# eCore_MCU.net
KiCad netlist of a schematic drawn in Altium Designer
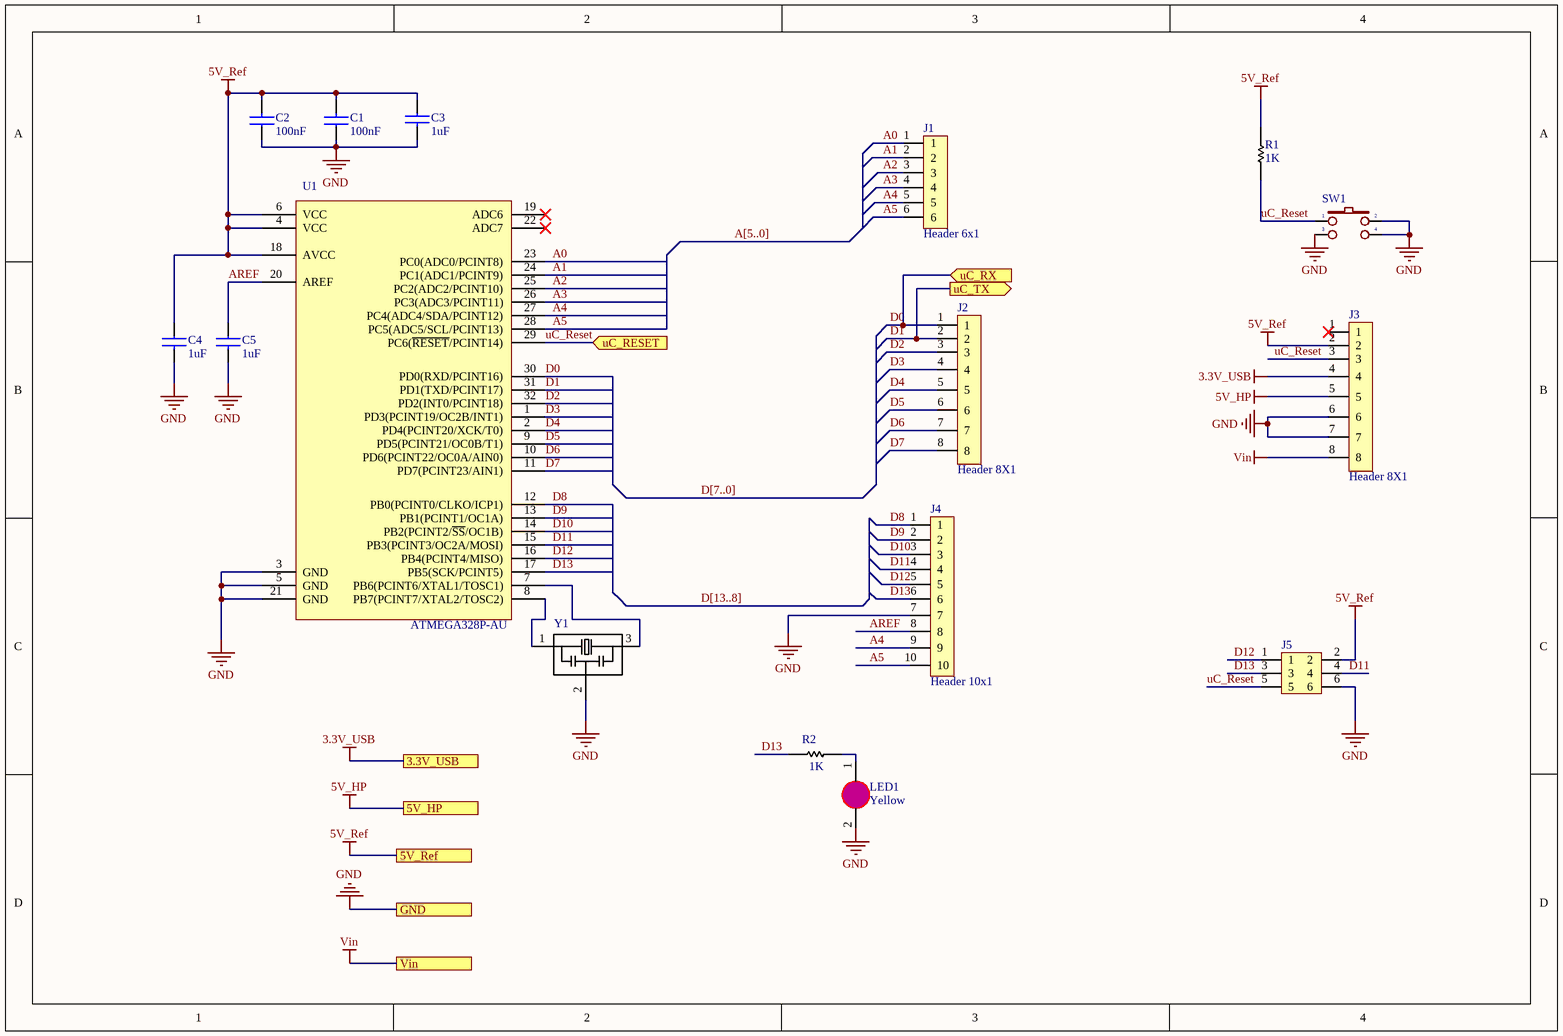
[diagram p0: eCore_MCU.SchDoc]

(export (version "E")
  (design (tool "Eeschema 10.0.6"))
  (components
    (comp (ref "C1")
      (value "100nF")
      (footprint "CAPC1005X60N")
      (libsource (lib "SCHP-CAD") (part "Cap 0402"))
    )
    (comp (ref "C2")
      (value "100nF")
      (footprint "CAPC1005X60N")
      (libsource (lib "SCHP-CAD") (part "Cap 0402"))
    )
    (comp (ref "C3") (value "1uF") (footprint "C0603") (libsource (lib "SCHP-CAD") (part "Cap 0603")))
    (comp (ref "C4") (value "1uF") (footprint "CAPC1005X60N") (libsource (lib "SCHP-CAD") (part "Cap 0402")))
    (comp (ref "C5") (value "1uF") (footprint "CAPC1005X60N") (libsource (lib "SCHP-CAD") (part "Cap 0402")))
    (comp (ref "J1")
      (value "Header 6x1")
      (footprint "1x6 Socket Heder 2.54mm")
      (libsource (lib "SCHP-CAD") (part "Header 6x1"))
    )
    (comp (ref "J2")
      (value "Header 8X1")
      (footprint "1x8 Socket Heder 2.54mm")
      (libsource (lib "SCHP-CAD") (part "Header 8X1"))
    )
    (comp (ref "J3")
      (value "Header 8X1")
      (footprint "1x8 Socket Heder 2.54mm")
      (libsource (lib "SCHP-CAD") (part "Header 8X1"))
    )
    (comp (ref "J4")
      (value "Header 10x1")
      (footprint "1x10 Socket Header 2.54mm")
      (libsource (lib "SCHP-CAD") (part "Header 10x1"))
    )
    (comp (ref "J5")
      (value "Header 3x2")
      (footprint "HEADER 3X3")
      (libsource (lib "SCHP-CAD") (part "Header 3x2"))
    )
    (comp (ref "LED1")
      (value "Yellow")
      (footprint "LEDY-0402")
      (description "LED 3mm")
      (libsource (lib "SCHP-CAD") (part "LEDSMD"))
    )
    (comp (ref "R1")
      (value "1K")
      (footprint "RES 0402 SMD")
      (description "Resistor")
      (fields
        (field (name "MANUFACTURER") "Generic Components")
        (field (name "PUBLISHER") "Altium Hobart Technology Centre")
      )
      (libsource (lib "SCHP-CAD") (part "Res 0402"))
    )
    (comp (ref "R2")
      (value "1K")
      (footprint "RES 0402 SMD")
      (description "Resistor")
      (fields
        (field (name "MANUFACTURER") "Generic Components")
        (field (name "PUBLISHER") "Altium Hobart Technology Centre")
      )
      (libsource (lib "SCHP-CAD") (part "Res 0402"))
    )
    (comp (ref "SW1")
      (value "SW2-SMD")
      (footprint "SW-SMD")
      (description "Switch button 2 pin")
      (libsource (lib "SCHP-CAD") (part "SW2-SMD"))
    )
    (comp (ref "U1")
      (value "ATMEGA328P-AU")
      (footprint "QFP80P900X900X120-32N")
      (description "ATmega Series 20 MHz 32 KB Flash 2 KB SRAM 8-Bit Microcontroller - TQFP-32")
      (fields (field (name "MF") "Atmel"))
      (libsource (lib "SCHP-CAD") (part "ATMEGA328P-AU"))
    )
    (comp (ref "Y1")
      (value "CSTCE16M0V53-R0")
      (footprint "OSC_CSTCE16M0V53-R0")
      (description "Ceramic Resonator 16MHz ??0.5% (Tol) ??0.3% (Stability) 15pF 40Ohm 3-Pin CSMD T/R")
      (fields (field (name "MF") "Murata"))
      (libsource (lib "SCHP-CAD") (part "XTAL-CSTCE16M0V53-R0"))
    )
  )
  (nets
    (net (code "1") (name "/A0") (class "Default")
      (node (ref "J1") (pin "1") (pinfunction "1_1") (pintype "passive"))
      (node (ref "U1") (pin "23") (pinfunction "PC0(ADC0/PCINT8)_23") (pintype "passive"))
    )
    (net (code "2") (name "/A1") (class "Default")
      (node (ref "J1") (pin "2") (pinfunction "2_2") (pintype "passive"))
      (node (ref "U1") (pin "24") (pinfunction "PC1(ADC1/PCINT9)_24") (pintype "passive"))
    )
    (net (code "3") (name "/A2") (class "Default")
      (node (ref "J1") (pin "3") (pinfunction "3_3") (pintype "passive"))
      (node (ref "U1") (pin "25") (pinfunction "PC2(ADC2/PCINT10)_25") (pintype "passive"))
    )
    (net (code "4") (name "/A3") (class "Default")
      (node (ref "J1") (pin "4") (pinfunction "4_4") (pintype "passive"))
      (node (ref "U1") (pin "26") (pinfunction "PC3(ADC3/PCINT11)_26") (pintype "passive"))
    )
    (net (code "5") (name "/A4") (class "Default")
      (node (ref "J1") (pin "5") (pinfunction "5_5") (pintype "passive"))
      (node (ref "J4") (pin "9") (pinfunction "9_9") (pintype "passive"))
      (node (ref "U1") (pin "27") (pinfunction "PC4(ADC4/SDA/PCINT12)_27") (pintype "passive"))
    )
    (net (code "6") (name "/A5") (class "Default")
      (node (ref "J1") (pin "6") (pinfunction "6_6") (pintype "passive"))
      (node (ref "J4") (pin "10") (pinfunction "10_10") (pintype "passive"))
      (node (ref "U1") (pin "28") (pinfunction "PC5(ADC5/SCL/PCINT13)_28") (pintype "passive"))
    )
    (net (code "7") (name "/AREF") (class "Default")
      (node (ref "C5") (pin "1") (pinfunction "1_1") (pintype "passive"))
      (node (ref "J4") (pin "8") (pinfunction "8_8") (pintype "passive"))
      (node (ref "U1") (pin "20") (pinfunction "AREF_20") (pintype "passive"))
    )
    (net (code "9") (name "/D0") (class "Default")
      (node (ref "J2") (pin "1") (pinfunction "1_1") (pintype "passive"))
      (node (ref "U1") (pin "30") (pinfunction "PD0(RXD/PCINT16)_30") (pintype "passive"))
    )
    (net (code "10") (name "/D1") (class "Default")
      (node (ref "J2") (pin "2") (pinfunction "2_2") (pintype "passive"))
      (node (ref "U1") (pin "31") (pinfunction "PD1(TXD/PCINT17)_31") (pintype "passive"))
    )
    (net (code "11") (name "/D2") (class "Default")
      (node (ref "J2") (pin "3") (pinfunction "3_3") (pintype "passive"))
      (node (ref "U1") (pin "32") (pinfunction "PD2(INT0/PCINT18)_32") (pintype "passive"))
    )
    (net (code "12") (name "/D3") (class "Default")
      (node (ref "J2") (pin "4") (pinfunction "4_4") (pintype "passive"))
      (node (ref "U1") (pin "1") (pinfunction "PD3(PCINT19/OC2B/INT1)_1") (pintype "passive"))
    )
    (net (code "13") (name "/D4") (class "Default")
      (node (ref "J2") (pin "5") (pinfunction "5_5") (pintype "passive"))
      (node (ref "U1") (pin "2") (pinfunction "PD4(PCINT20/XCK/T0)_2") (pintype "passive"))
    )
    (net (code "14") (name "/D5") (class "Default")
      (node (ref "J2") (pin "6") (pinfunction "6_6") (pintype "passive"))
      (node (ref "U1") (pin "9") (pinfunction "PD5(PCINT21/OC0B/T1)_9") (pintype "passive"))
    )
    (net (code "15") (name "/D6") (class "Default")
      (node (ref "J2") (pin "7") (pinfunction "7_7") (pintype "passive"))
      (node (ref "U1") (pin "10") (pinfunction "PD6(PCINT22/OC0A/AIN0)_10") (pintype "passive"))
    )
    (net (code "16") (name "/D7") (class "Default")
      (node (ref "J2") (pin "8") (pinfunction "8_8") (pintype "passive"))
      (node (ref "U1") (pin "11") (pinfunction "PD7(PCINT23/AIN1)_11") (pintype "passive"))
    )
    (net (code "17") (name "/D8") (class "Default")
      (node (ref "J4") (pin "1") (pinfunction "1_1") (pintype "passive"))
      (node (ref "U1") (pin "12") (pinfunction "PB0(PCINT0/CLKO/ICP1)_12") (pintype "passive"))
    )
    (net (code "18") (name "/D9") (class "Default")
      (node (ref "J4") (pin "2") (pinfunction "2_2") (pintype "passive"))
      (node (ref "U1") (pin "13") (pinfunction "PB1(PCINT1/OC1A)_13") (pintype "passive"))
    )
    (net (code "19") (name "/D10") (class "Default")
      (node (ref "J4") (pin "3") (pinfunction "3_3") (pintype "passive"))
      (node (ref "U1") (pin "14") (pinfunction "PB2(PCINT2/~{SS}/OC1B)_14") (pintype "passive"))
    )
    (net (code "20") (name "/D11") (class "Default")
      (node (ref "J4") (pin "4") (pinfunction "4_4") (pintype "passive"))
      (node (ref "J5") (pin "4") (pinfunction "4_4") (pintype "passive"))
      (node (ref "U1") (pin "15") (pinfunction "PB3(PCINT3/OC2A/MOSI)_15") (pintype "passive"))
    )
    (net (code "21") (name "/D12") (class "Default")
      (node (ref "J4") (pin "5") (pinfunction "5_5") (pintype "passive"))
      (node (ref "J5") (pin "1") (pinfunction "1_1") (pintype "passive"))
      (node (ref "U1") (pin "16") (pinfunction "PB4(PCINT4/MISO)_16") (pintype "passive"))
    )
    (net (code "22") (name "/D13") (class "Default")
      (node (ref "J4") (pin "6") (pinfunction "6_6") (pintype "passive"))
      (node (ref "J5") (pin "3") (pinfunction "3_3") (pintype "passive"))
      (node (ref "R2") (pin "1") (pinfunction "1_1") (pintype "passive"))
      (node (ref "U1") (pin "17") (pinfunction "PB5(SCK/PCINT5)_17") (pintype "passive"))
    )
    (net (code "25") (name "/uC_Reset") (class "Default")
      (node (ref "J3") (pin "3") (pinfunction "3_3") (pintype "passive"))
      (node (ref "J5") (pin "5") (pinfunction "5_5") (pintype "passive"))
      (node (ref "R1") (pin "1") (pinfunction "1_1") (pintype "passive"))
      (node (ref "SW1") (pin "1") (pinfunction "1_1") (pintype "passive"))
      (node (ref "U1") (pin "29") (pinfunction "PC6(~{RESET}/PCINT14)_29") (pintype "passive"))
    )
    (net (code "26") (name "3.3V_USB") (class "Default")
      (node (ref "J3") (pin "4") (pinfunction "4_4") (pintype "passive"))
    )
    (net (code "27") (name "5V_HP") (class "Default")
      (node (ref "J3") (pin "5") (pinfunction "5_5") (pintype "passive"))
    )
    (net (code "28") (name "5V_Ref") (class "Default")
      (node (ref "C1") (pin "2") (pinfunction "2_2") (pintype "passive"))
      (node (ref "C2") (pin "2") (pinfunction "2_2") (pintype "passive"))
      (node (ref "C3") (pin "1") (pinfunction "1_1") (pintype "passive"))
      (node (ref "C4") (pin "1") (pinfunction "1_1") (pintype "passive"))
      (node (ref "J3") (pin "2") (pinfunction "2_2") (pintype "passive"))
      (node (ref "J5") (pin "2") (pinfunction "2_2") (pintype "passive"))
      (node (ref "R1") (pin "2") (pinfunction "2_2") (pintype "passive"))
      (node (ref "U1") (pin "18") (pinfunction "AVCC_18") (pintype "passive"))
      (node (ref "U1") (pin "4") (pinfunction "VCC_4") (pintype "passive"))
      (node (ref "U1") (pin "6") (pinfunction "VCC_6") (pintype "passive"))
    )
    (net (code "29") (name "GND") (class "Default")
      (node (ref "C1") (pin "1") (pinfunction "1_1") (pintype "passive"))
      (node (ref "C2") (pin "1") (pinfunction "1_1") (pintype "passive"))
      (node (ref "C3") (pin "2") (pinfunction "2_2") (pintype "passive"))
      (node (ref "C4") (pin "2") (pinfunction "2_2") (pintype "passive"))
      (node (ref "C5") (pin "2") (pinfunction "2_2") (pintype "passive"))
      (node (ref "J3") (pin "6") (pinfunction "6_6") (pintype "passive"))
      (node (ref "J3") (pin "7") (pinfunction "7_7") (pintype "passive"))
      (node (ref "J4") (pin "7") (pinfunction "7_7") (pintype "passive"))
      (node (ref "J5") (pin "6") (pinfunction "6_6") (pintype "passive"))
      (node (ref "LED1") (pin "2") (pinfunction "K_2") (pintype "passive"))
      (node (ref "SW1") (pin "2") (pinfunction "2_2") (pintype "passive"))
      (node (ref "SW1") (pin "S1") (pinfunction "S1_S1") (pintype "passive"))
      (node (ref "SW1") (pin "S2") (pinfunction "S2_S2") (pintype "passive"))
      (node (ref "U1") (pin "21") (pinfunction "GND_21") (pintype "passive"))
      (node (ref "U1") (pin "3") (pinfunction "GND_3") (pintype "passive"))
      (node (ref "U1") (pin "5") (pinfunction "GND_5") (pintype "passive"))
      (node (ref "Y1") (pin "2") (pinfunction "2_2") (pintype "power_in"))
    )
    (net (code "30") (name "Net-(LED1-A)") (class "Default")
      (node (ref "LED1") (pin "1") (pinfunction "A_1") (pintype "passive"))
      (node (ref "R2") (pin "2") (pinfunction "2_2") (pintype "passive"))
    )
    (net (code "31") (name "Net-(U1-PB6(PCINT6{slash}XTAL1{slash}TOSC1))") (class "Default")
      (node (ref "U1") (pin "7") (pinfunction "PB6(PCINT6/XTAL1/TOSC1)_7") (pintype "passive"))
      (node (ref "Y1") (pin "3") (pinfunction "3_3") (pintype "passive"))
    )
    (net (code "32") (name "Net-(U1-PB7(PCINT7{slash}XTAL2{slash}TOSC2))") (class "Default")
      (node (ref "U1") (pin "8") (pinfunction "PB7(PCINT7/XTAL2/TOSC2)_8") (pintype "passive"))
      (node (ref "Y1") (pin "1") (pinfunction "1_1") (pintype "passive"))
    )
    (net (code "33") (name "Vin") (class "Default")
      (node (ref "J3") (pin "8") (pinfunction "8_8") (pintype "passive"))
    )
    (net (code "34") (name "unconnected-(J3-Pad1)") (class "Default")
      (node (ref "J3") (pin "1") (pinfunction "1_1") (pintype "passive+no_connect"))
    )
    (net (code "35") (name "unconnected-(U1-ADC6-Pad19)") (class "Default")
      (node (ref "U1") (pin "19") (pinfunction "ADC6_19") (pintype "passive+no_connect"))
    )
    (net (code "36") (name "unconnected-(U1-ADC7-Pad22)") (class "Default")
      (node (ref "U1") (pin "22") (pinfunction "ADC7_22") (pintype "passive+no_connect"))
    )
  )
)
